# 20240102-fresh_air_control.net
KiCad netlist of a schematic drawn in EAGLE
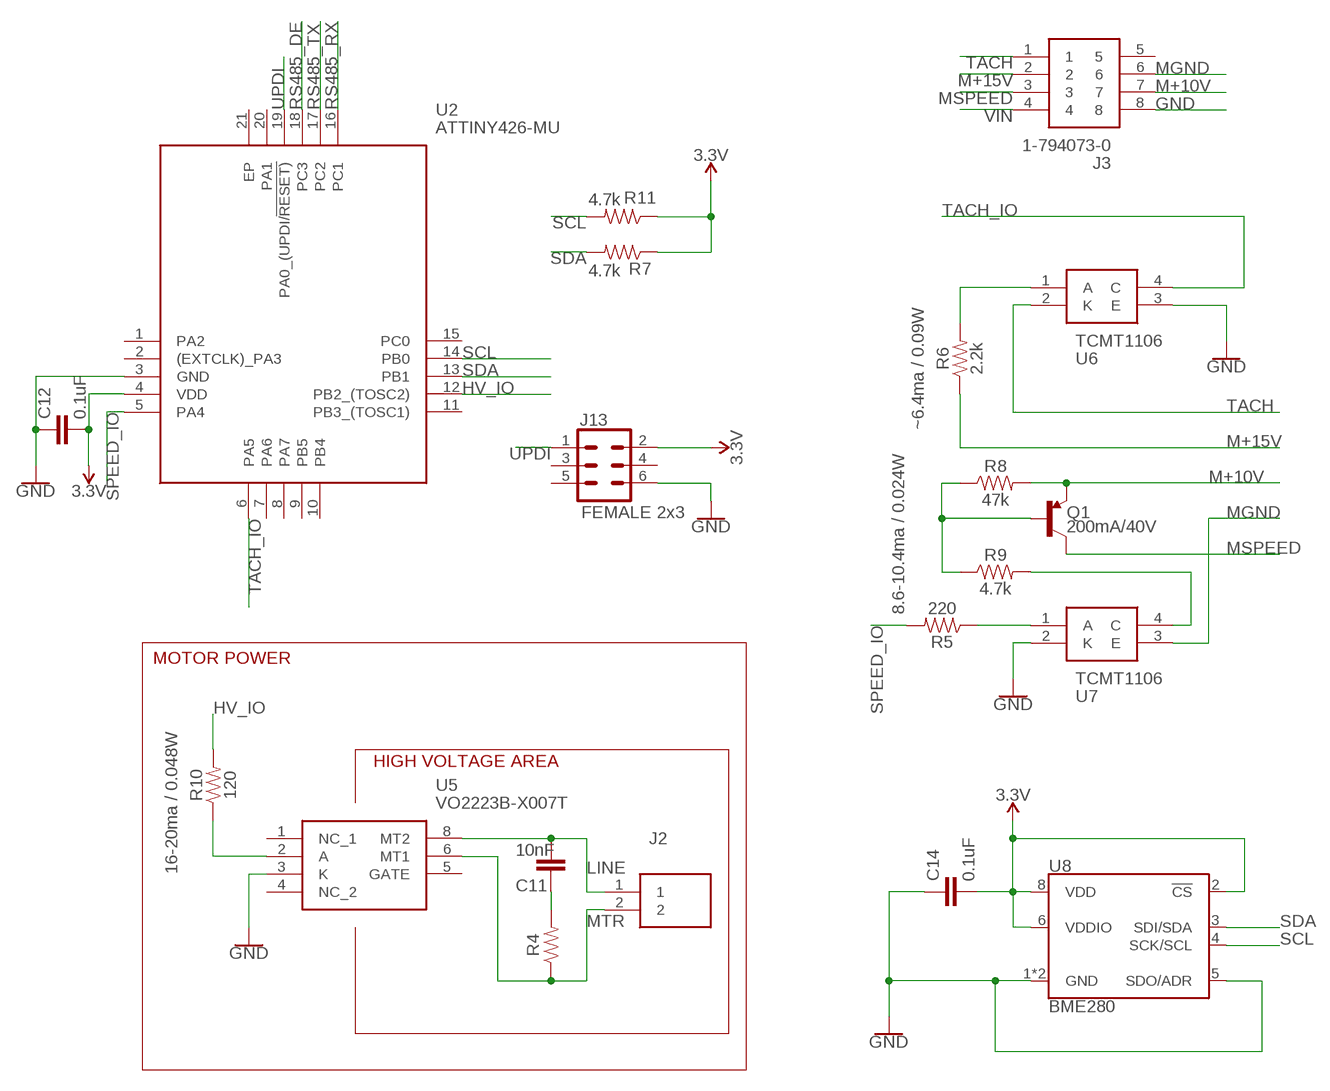
[diagram p0: schematic, sheet 1]
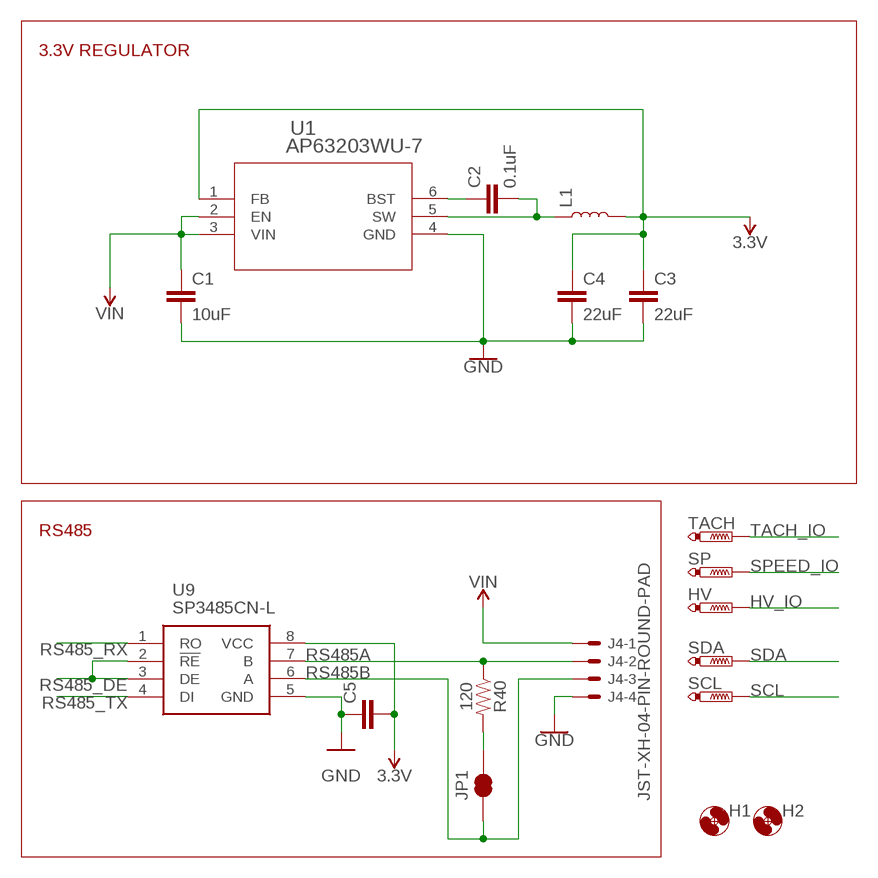
[diagram p1: schematic, sheet 2]

(export (version "E")
  (design (tool "Eeschema 10.0.6"))
  (components
    (comp (ref "C11")
      (value "10nF")
      (footprint "eagle-import:0805")
      (libsource (lib "eagle-import") (part "10NF-0805-400V-20%"))
    )
    (comp (ref "C12")
      (value "0.1uF")
      (footprint "eagle-import:0603")
      (libsource (lib "eagle-import") (part "0.1UF-0603-25V-5%"))
    )
    (comp (ref "C14")
      (value "0.1uF")
      (footprint "eagle-import:0603")
      (libsource (lib "eagle-import") (part "0.1UF-0603-25V-5%"))
    )
    (comp (ref "J2")
      (value "1-770166-0")
      (footprint "eagle-import:17701660")
      (fields (field (name "MOUSER_PART_NUMBER") "571-1-770166-0"))
      (libsource (lib "eagle-import") (part "1-770166-0"))
    )
    (comp (ref "J3")
      (value "1-794073-0")
      (footprint "eagle-import:17940730")
      (fields (field (name "MOUSER_PART_NUMBER") "571-1-794073-0"))
      (libsource (lib "eagle-import") (part "1-794073-0"))
    )
    (comp (ref "J13")
      (value "FEMALE 2x3")
      (footprint "eagle-import:2X3")
      (libsource (lib "eagle-import") (part "CONN_03X2FEMALE"))
    )
    (comp (ref "Q1")
      (value "200mA/40V")
      (footprint "eagle-import:SOT23-3")
      (libsource (lib "eagle-import") (part "TRANS_PNP-PMBT3906|MMBT3906L"))
    )
    (comp (ref "R4")
      (value "100")
      (footprint "eagle-import:0805")
      (libsource (lib "eagle-import") (part "100OHM-0805-1/10W-5%-400V"))
    )
    (comp (ref "R5")
      (value "220")
      (footprint "eagle-import:0603")
      (libsource (lib "eagle-import") (part "220OHM-0603-1/10W-1%"))
    )
    (comp (ref "R6")
      (value "2.2k")
      (footprint "eagle-import:0603")
      (libsource (lib "eagle-import") (part "2.2KOHM-0603-1/10W-1%"))
    )
    (comp (ref "R7")
      (value "4.7k")
      (footprint "eagle-import:0603")
      (libsource (lib "eagle-import") (part "4.7KOHM-0603-1/10W-1%"))
    )
    (comp (ref "R8")
      (value "47k")
      (footprint "eagle-import:0603")
      (libsource (lib "eagle-import") (part "47KOHM-0603-1/10W-1%"))
    )
    (comp (ref "R9")
      (value "4.7k")
      (footprint "eagle-import:0603")
      (libsource (lib "eagle-import") (part "4.7KOHM-0603-1/10W-1%"))
    )
    (comp (ref "R10")
      (value "120")
      (footprint "eagle-import:0603")
      (libsource (lib "eagle-import") (part "120OHM-0603-1/10W-5%"))
    )
    (comp (ref "R11")
      (value "4.7k")
      (footprint "eagle-import:0603")
      (libsource (lib "eagle-import") (part "4.7KOHM-0603-1/10W-1%"))
    )
    (comp (ref "U2")
      (value "ATTINY426-MU")
      (footprint "eagle-import:QFN40P300X300X90-21N")
      (fields (field (name "MOUSER_PART_NUMBER") "579-ATTINY426-MU"))
      (libsource (lib "eagle-import") (part "ATTINY426-MU"))
    )
    (comp (ref "U5")
      (value "VO2223B-X007T")
      (footprint "eagle-import:VO2223BX007T")
      (fields (field (name "MOUSER_PART_NUMBER") "78-VO2223B-X007T"))
      (libsource (lib "eagle-import") (part "VO2223B-X007T"))
    )
    (comp (ref "U6")
      (value "TCMT1106")
      (footprint "eagle-import:SOIC127P700X230-4N")
      (fields (field (name "MOUSER_PART_NUMBER") "782-TCMT1106"))
      (libsource (lib "eagle-import") (part "TCMT1106"))
    )
    (comp (ref "U7")
      (value "TCMT1106")
      (footprint "eagle-import:SOIC127P700X230-4N")
      (fields (field (name "MOUSER_PART_NUMBER") "782-TCMT1106"))
      (libsource (lib "eagle-import") (part "TCMT1106"))
    )
    (comp (ref "U8")
      (value "BME280")
      (footprint "eagle-import:LGA-8-2.5X2.5")
      (libsource (lib "eagle-import") (part "BME280"))
    )
    (comp (ref "C1")
      (value "10uF")
      (footprint "eagle-import:1206")
      (libsource (lib "eagle-import") (part "10UF-1206-6.3V-20%"))
    )
    (comp (ref "C2")
      (value "0.1uF")
      (footprint "eagle-import:0603")
      (libsource (lib "eagle-import") (part "0.1UF-0603-25V-5%"))
    )
    (comp (ref "C3")
      (value "22uF")
      (footprint "eagle-import:0805")
      (libsource (lib "eagle-import") (part "22UF-0805-6.3V-20%"))
    )
    (comp (ref "C4")
      (value "22uF")
      (footprint "eagle-import:0805")
      (libsource (lib "eagle-import") (part "22UF-0805-6.3V-20%"))
    )
    (comp (ref "C5")
      (value "0.1uF")
      (footprint "eagle-import:0603")
      (libsource (lib "eagle-import") (part "0.1UF-0603-25V-5%"))
    )
    (comp (ref "H1")
      (value "MOUNT-HOLE3.3")
      (footprint "eagle-import:3,3")
      (libsource (lib "eagle-import") (part "MOUNT-HOLE3.3"))
    )
    (comp (ref "H2")
      (value "MOUNT-HOLE3.3")
      (footprint "eagle-import:3,3")
      (libsource (lib "eagle-import") (part "MOUNT-HOLE3.3"))
    )
    (comp (ref "HV")
      (value "PTR1B1,27")
      (footprint "eagle-import:B1,27")
      (libsource (lib "eagle-import") (part "PTR1B1,27"))
    )
    (comp (ref "J4")
      (value "JST-XH-04-PIN-ROUND-PAD")
      (footprint "eagle-import:JST-XH-04-PACKAGE-ROUND-PAD")
      (libsource (lib "eagle-import") (part "JST-XH-04-PIN-ROUND-PAD"))
    )
    (comp (ref "JP1")
      (value "JUMPER-SMT_2_NC_TRACE_NO-SILK")
      (footprint "eagle-import:SMT-JUMPER_2_NC_TRACE_NO-SILK")
      (libsource (lib "eagle-import") (part "JUMPER-SMT_2_NC_TRACE_NO-SILK"))
    )
    (comp (ref "L1")
      (value "4.7μH_SHIELDED_INDUCTOR")
      (footprint "eagle-import:1008(2520)")
      (libsource (lib "eagle-import") (part "4.7μH_SHIELDED_INDUCTOR"))
    )
    (comp (ref "R40")
      (value "120")
      (footprint "eagle-import:0603")
      (libsource (lib "eagle-import") (part "120OHM-0603-1/10W-5%"))
    )
    (comp (ref "SCL")
      (value "PTR1B1,27")
      (footprint "eagle-import:B1,27")
      (libsource (lib "eagle-import") (part "PTR1B1,27"))
    )
    (comp (ref "SDA")
      (value "PTR1B1,27")
      (footprint "eagle-import:B1,27")
      (libsource (lib "eagle-import") (part "PTR1B1,27"))
    )
    (comp (ref "SP")
      (value "PTR1B1,27")
      (footprint "eagle-import:B1,27")
      (libsource (lib "eagle-import") (part "PTR1B1,27"))
    )
    (comp (ref "TACH")
      (value "PTR1B1,27")
      (footprint "eagle-import:B1,27")
      (libsource (lib "eagle-import") (part "PTR1B1,27"))
    )
    (comp (ref "U1")
      (value "AP63203WU-7")
      (footprint "eagle-import:SOIC_05WU-7_DIO")
      (fields (field (name "COPYRIGHT") "Copyright (C) 2023 Ultra Librarian. All rights reserved."))
      (libsource (lib "eagle-import") (part "AP63203WU-7"))
    )
    (comp (ref "U9")
      (value "SP3485CN-L")
      (footprint "eagle-import:SOIC127P600X175-8N")
      (fields (field (name "MOUSER_PART_NUMBER") "701-SP3485CN-L"))
      (libsource (lib "eagle-import") (part "SP3485CN-L"))
    )
  )
  (nets
    (net (code "1") (name "3.3V") (class "Default")
      (node (ref "C12") (pin "2") (pinfunction "2_2") (pintype "passive"))
      (node (ref "C14") (pin "2") (pinfunction "2_2") (pintype "passive"))
      (node (ref "C3") (pin "1") (pinfunction "1_1") (pintype "passive"))
      (node (ref "C4") (pin "1") (pinfunction "1_1") (pintype "passive"))
      (node (ref "C5") (pin "2") (pinfunction "2_2") (pintype "passive"))
      (node (ref "J13") (pin "2") (pinfunction "2_2") (pintype "bidirectional"))
      (node (ref "L1") (pin "2") (pinfunction "2_2") (pintype "passive"))
      (node (ref "R11") (pin "1") (pinfunction "1_1") (pintype "passive"))
      (node (ref "R7") (pin "1") (pinfunction "1_1") (pintype "passive"))
      (node (ref "U1") (pin "1") (pinfunction "FB_1") (pintype "passive"))
      (node (ref "U2") (pin "4") (pinfunction "VDD_4") (pintype "bidirectional"))
      (node (ref "U8") (pin "2") (pinfunction "~{CS}_2") (pintype "bidirectional"))
      (node (ref "U8") (pin "6") (pinfunction "VDDIO_6") (pintype "bidirectional"))
      (node (ref "U8") (pin "8") (pinfunction "VDD_8") (pintype "bidirectional"))
      (node (ref "U9") (pin "8") (pinfunction "VCC_8") (pintype "bidirectional"))
    )
    (net (code "2") (name "GND") (class "Default")
      (node (ref "C1") (pin "2") (pinfunction "2_2") (pintype "passive"))
      (node (ref "C12") (pin "1") (pinfunction "1_1") (pintype "passive"))
      (node (ref "C14") (pin "1") (pinfunction "1_1") (pintype "passive"))
      (node (ref "C3") (pin "2") (pinfunction "2_2") (pintype "passive"))
      (node (ref "C4") (pin "2") (pinfunction "2_2") (pintype "passive"))
      (node (ref "C5") (pin "1") (pinfunction "1_1") (pintype "passive"))
      (node (ref "J13") (pin "6") (pinfunction "6_6") (pintype "bidirectional"))
      (node (ref "J3") (pin "8") (pinfunction "8_8") (pintype "bidirectional"))
      (node (ref "J4") (pin "4") (pinfunction "S_4") (pintype "passive"))
      (node (ref "U1") (pin "4") (pinfunction "GND_4") (pintype "passive"))
      (node (ref "U2") (pin "3") (pinfunction "GND_3") (pintype "bidirectional"))
      (node (ref "U5") (pin "3") (pinfunction "K_3") (pintype "bidirectional"))
      (node (ref "U6") (pin "3") (pinfunction "E_3") (pintype "bidirectional"))
      (node (ref "U7") (pin "2") (pinfunction "K_2") (pintype "bidirectional"))
      (node (ref "U8") (pin "1") (pinfunction "GND_1") (pintype "bidirectional"))
      (node (ref "U8") (pin "5") (pinfunction "SDO/ADR_5") (pintype "bidirectional"))
      (node (ref "U8") (pin "7") (pinfunction "GND_7") (pintype "bidirectional"))
      (node (ref "U9") (pin "5") (pinfunction "GND_5") (pintype "bidirectional"))
    )
    (net (code "3") (name "HV_IO") (class "Default")
      (node (ref "HV") (pin "TP") (pinfunction "TP_TP") (pintype "input"))
      (node (ref "R10") (pin "2") (pinfunction "2_2") (pintype "passive"))
      (node (ref "U2") (pin "12") (pinfunction "PB2_(TOSC2)_12") (pintype "bidirectional"))
    )
    (net (code "4") (name "LINE") (class "Default")
      (node (ref "C11") (pin "1") (pinfunction "1_1") (pintype "passive"))
      (node (ref "J2") (pin "1") (pinfunction "1_1") (pintype "bidirectional"))
      (node (ref "U5") (pin "8") (pinfunction "MT2_8") (pintype "bidirectional"))
    )
    (net (code "5") (name "M+10V") (class "Default")
      (node (ref "J3") (pin "7") (pinfunction "7_7") (pintype "bidirectional"))
      (node (ref "Q1") (pin "2") (pinfunction "E_2") (pintype "passive"))
      (node (ref "R8") (pin "2") (pinfunction "2_2") (pintype "passive"))
    )
    (net (code "6") (name "M+15V") (class "Default")
      (node (ref "J3") (pin "2") (pinfunction "2_2") (pintype "bidirectional"))
      (node (ref "R6") (pin "1") (pinfunction "1_1") (pintype "passive"))
    )
    (net (code "7") (name "MGND") (class "Default")
      (node (ref "J3") (pin "6") (pinfunction "6_6") (pintype "bidirectional"))
      (node (ref "U7") (pin "3") (pinfunction "E_3") (pintype "bidirectional"))
    )
    (net (code "8") (name "MSPEED") (class "Default")
      (node (ref "J3") (pin "3") (pinfunction "3_3") (pintype "bidirectional"))
      (node (ref "Q1") (pin "3") (pinfunction "C_3") (pintype "passive"))
    )
    (net (code "9") (name "MTR") (class "Default")
      (node (ref "J2") (pin "2") (pinfunction "2_2") (pintype "bidirectional"))
      (node (ref "R4") (pin "1") (pinfunction "1_1") (pintype "passive"))
      (node (ref "U5") (pin "6") (pinfunction "MT1_6") (pintype "bidirectional"))
    )
    (net (code "10") (name "Net-(C11-Pad2)") (class "Default")
      (node (ref "C11") (pin "2") (pinfunction "2_2") (pintype "passive"))
      (node (ref "R4") (pin "2") (pinfunction "2_2") (pintype "passive"))
    )
    (net (code "11") (name "Net-(JP1-Pad2)") (class "Default")
      (node (ref "JP1") (pin "2") (pinfunction "2_2") (pintype "passive"))
      (node (ref "R40") (pin "2") (pinfunction "2_2") (pintype "passive"))
    )
    (net (code "12") (name "Net-(Q1-B)") (class "Default")
      (node (ref "Q1") (pin "1") (pinfunction "B_1") (pintype "passive"))
      (node (ref "R8") (pin "1") (pinfunction "1_1") (pintype "passive"))
      (node (ref "R9") (pin "1") (pinfunction "1_1") (pintype "passive"))
    )
    (net (code "13") (name "Net-(U1-BST)") (class "Default")
      (node (ref "C2") (pin "1") (pinfunction "1_1") (pintype "passive"))
      (node (ref "U1") (pin "6") (pinfunction "BST_6") (pintype "passive"))
    )
    (net (code "14") (name "Net-(U1-SW)") (class "Default")
      (node (ref "C2") (pin "2") (pinfunction "2_2") (pintype "passive"))
      (node (ref "L1") (pin "1") (pinfunction "1_1") (pintype "passive"))
      (node (ref "U1") (pin "5") (pinfunction "SW_5") (pintype "passive"))
    )
    (net (code "15") (name "Net-(U5-A)") (class "Default")
      (node (ref "R10") (pin "1") (pinfunction "1_1") (pintype "passive"))
      (node (ref "U5") (pin "2") (pinfunction "A_2") (pintype "bidirectional"))
    )
    (net (code "16") (name "Net-(U6-A)") (class "Default")
      (node (ref "R6") (pin "2") (pinfunction "2_2") (pintype "passive"))
      (node (ref "U6") (pin "1") (pinfunction "A_1") (pintype "bidirectional"))
    )
    (net (code "17") (name "Net-(U7-A)") (class "Default")
      (node (ref "R5") (pin "1") (pinfunction "1_1") (pintype "passive"))
      (node (ref "U7") (pin "1") (pinfunction "A_1") (pintype "bidirectional"))
    )
    (net (code "18") (name "Net-(U7-C)") (class "Default")
      (node (ref "R9") (pin "2") (pinfunction "2_2") (pintype "passive"))
      (node (ref "U7") (pin "4") (pinfunction "C_4") (pintype "bidirectional"))
    )
    (net (code "19") (name "RS485A") (class "Default")
      (node (ref "J4") (pin "2") (pinfunction "S_2") (pintype "passive"))
      (node (ref "R40") (pin "1") (pinfunction "1_1") (pintype "passive"))
      (node (ref "U9") (pin "7") (pinfunction "B_7") (pintype "bidirectional"))
    )
    (net (code "20") (name "RS485B") (class "Default")
      (node (ref "J4") (pin "3") (pinfunction "S_3") (pintype "passive"))
      (node (ref "JP1") (pin "1") (pinfunction "1_1") (pintype "passive"))
      (node (ref "U9") (pin "6") (pinfunction "A_6") (pintype "bidirectional"))
    )
    (net (code "21") (name "RS485_DE") (class "Default")
      (node (ref "U2") (pin "18") (pinfunction "PC3_18") (pintype "bidirectional"))
      (node (ref "U9") (pin "2") (pinfunction "~{RE}_2") (pintype "bidirectional"))
      (node (ref "U9") (pin "3") (pinfunction "DE_3") (pintype "bidirectional"))
    )
    (net (code "22") (name "RS485_RX") (class "Default")
      (node (ref "U2") (pin "16") (pinfunction "PC1_16") (pintype "bidirectional"))
      (node (ref "U9") (pin "1") (pinfunction "RO_1") (pintype "bidirectional"))
    )
    (net (code "23") (name "RS485_TX") (class "Default")
      (node (ref "U2") (pin "17") (pinfunction "PC2_17") (pintype "bidirectional"))
      (node (ref "U9") (pin "4") (pinfunction "DI_4") (pintype "bidirectional"))
    )
    (net (code "24") (name "SCL") (class "Default")
      (node (ref "R11") (pin "2") (pinfunction "2_2") (pintype "passive"))
      (node (ref "SCL") (pin "TP") (pinfunction "TP_TP") (pintype "input"))
      (node (ref "U2") (pin "14") (pinfunction "PB0_14") (pintype "bidirectional"))
      (node (ref "U8") (pin "4") (pinfunction "SCK/SCL_4") (pintype "bidirectional"))
    )
    (net (code "25") (name "SDA") (class "Default")
      (node (ref "R7") (pin "2") (pinfunction "2_2") (pintype "passive"))
      (node (ref "SDA") (pin "TP") (pinfunction "TP_TP") (pintype "input"))
      (node (ref "U2") (pin "13") (pinfunction "PB1_13") (pintype "bidirectional"))
      (node (ref "U8") (pin "3") (pinfunction "SDI/SDA_3") (pintype "bidirectional"))
    )
    (net (code "26") (name "SPEED_IO") (class "Default")
      (node (ref "R5") (pin "2") (pinfunction "2_2") (pintype "passive"))
      (node (ref "SP") (pin "TP") (pinfunction "TP_TP") (pintype "input"))
      (node (ref "U2") (pin "5") (pinfunction "PA4_5") (pintype "bidirectional"))
    )
    (net (code "27") (name "TACH") (class "Default")
      (node (ref "J3") (pin "1") (pinfunction "1_1") (pintype "bidirectional"))
      (node (ref "U6") (pin "2") (pinfunction "K_2") (pintype "bidirectional"))
    )
    (net (code "28") (name "TACH_IO") (class "Default")
      (node (ref "TACH") (pin "TP") (pinfunction "TP_TP") (pintype "input"))
      (node (ref "U2") (pin "6") (pinfunction "PA5_6") (pintype "bidirectional"))
      (node (ref "U6") (pin "4") (pinfunction "C_4") (pintype "bidirectional"))
    )
    (net (code "29") (name "UPDI") (class "Default")
      (node (ref "J13") (pin "1") (pinfunction "1_1") (pintype "bidirectional"))
      (node (ref "U2") (pin "19") (pinfunction "PA0_(UPDI/~{RESET})_19") (pintype "bidirectional"))
    )
    (net (code "30") (name "VIN") (class "Default")
      (node (ref "C1") (pin "1") (pinfunction "1_1") (pintype "passive"))
      (node (ref "J3") (pin "4") (pinfunction "4_4") (pintype "bidirectional"))
      (node (ref "J4") (pin "1") (pinfunction "S_1") (pintype "passive"))
      (node (ref "U1") (pin "2") (pinfunction "EN_2") (pintype "passive"))
      (node (ref "U1") (pin "3") (pinfunction "VIN_3") (pintype "passive"))
    )
    (net (code "31") (name "unconnected-(J3-Pad5)") (class "Default")
      (node (ref "J3") (pin "5") (pinfunction "5_5") (pintype "bidirectional"))
    )
    (net (code "32") (name "unconnected-(J13-Pad3)") (class "Default")
      (node (ref "J13") (pin "3") (pinfunction "3_3") (pintype "bidirectional"))
    )
    (net (code "33") (name "unconnected-(J13-Pad4)") (class "Default")
      (node (ref "J13") (pin "4") (pinfunction "4_4") (pintype "bidirectional"))
    )
    (net (code "34") (name "unconnected-(J13-Pad5)") (class "Default")
      (node (ref "J13") (pin "5") (pinfunction "5_5") (pintype "bidirectional"))
    )
    (net (code "35") (name "unconnected-(U2-(EXTCLK)_PA3-Pad2)") (class "Default")
      (node (ref "U2") (pin "2") (pinfunction "(EXTCLK)_PA3_2") (pintype "bidirectional"))
    )
    (net (code "36") (name "unconnected-(U2-EP-Pad21)") (class "Default")
      (node (ref "U2") (pin "21") (pinfunction "EP_21") (pintype "bidirectional"))
    )
    (net (code "37") (name "unconnected-(U2-PA1-Pad20)") (class "Default")
      (node (ref "U2") (pin "20") (pinfunction "PA1_20") (pintype "bidirectional"))
    )
    (net (code "38") (name "unconnected-(U2-PA2-Pad1)") (class "Default")
      (node (ref "U2") (pin "1") (pinfunction "PA2_1") (pintype "bidirectional"))
    )
    (net (code "39") (name "unconnected-(U2-PA6-Pad7)") (class "Default")
      (node (ref "U2") (pin "7") (pinfunction "PA6_7") (pintype "bidirectional"))
    )
    (net (code "40") (name "unconnected-(U2-PA7-Pad8)") (class "Default")
      (node (ref "U2") (pin "8") (pinfunction "PA7_8") (pintype "bidirectional"))
    )
    (net (code "41") (name "unconnected-(U2-PB3_(TOSC1)-Pad11)") (class "Default")
      (node (ref "U2") (pin "11") (pinfunction "PB3_(TOSC1)_11") (pintype "bidirectional"))
    )
    (net (code "42") (name "unconnected-(U2-PB4-Pad10)") (class "Default")
      (node (ref "U2") (pin "10") (pinfunction "PB4_10") (pintype "bidirectional"))
    )
    (net (code "43") (name "unconnected-(U2-PB5-Pad9)") (class "Default")
      (node (ref "U2") (pin "9") (pinfunction "PB5_9") (pintype "bidirectional"))
    )
    (net (code "44") (name "unconnected-(U2-PC0-Pad15)") (class "Default")
      (node (ref "U2") (pin "15") (pinfunction "PC0_15") (pintype "bidirectional"))
    )
    (net (code "45") (name "unconnected-(U5-GATE-Pad5)") (class "Default")
      (node (ref "U5") (pin "5") (pinfunction "GATE_5") (pintype "bidirectional"))
    )
    (net (code "46") (name "unconnected-(U5-NC_1-Pad1)") (class "Default")
      (node (ref "U5") (pin "1") (pinfunction "NC_1_1") (pintype "bidirectional"))
    )
    (net (code "47") (name "unconnected-(U5-NC_2-Pad4)") (class "Default")
      (node (ref "U5") (pin "4") (pinfunction "NC_2_4") (pintype "bidirectional"))
    )
  )
)
